# 12vTo5vPowerSupplyBoard.net
KiCad netlist of a schematic drawn in EAGLE
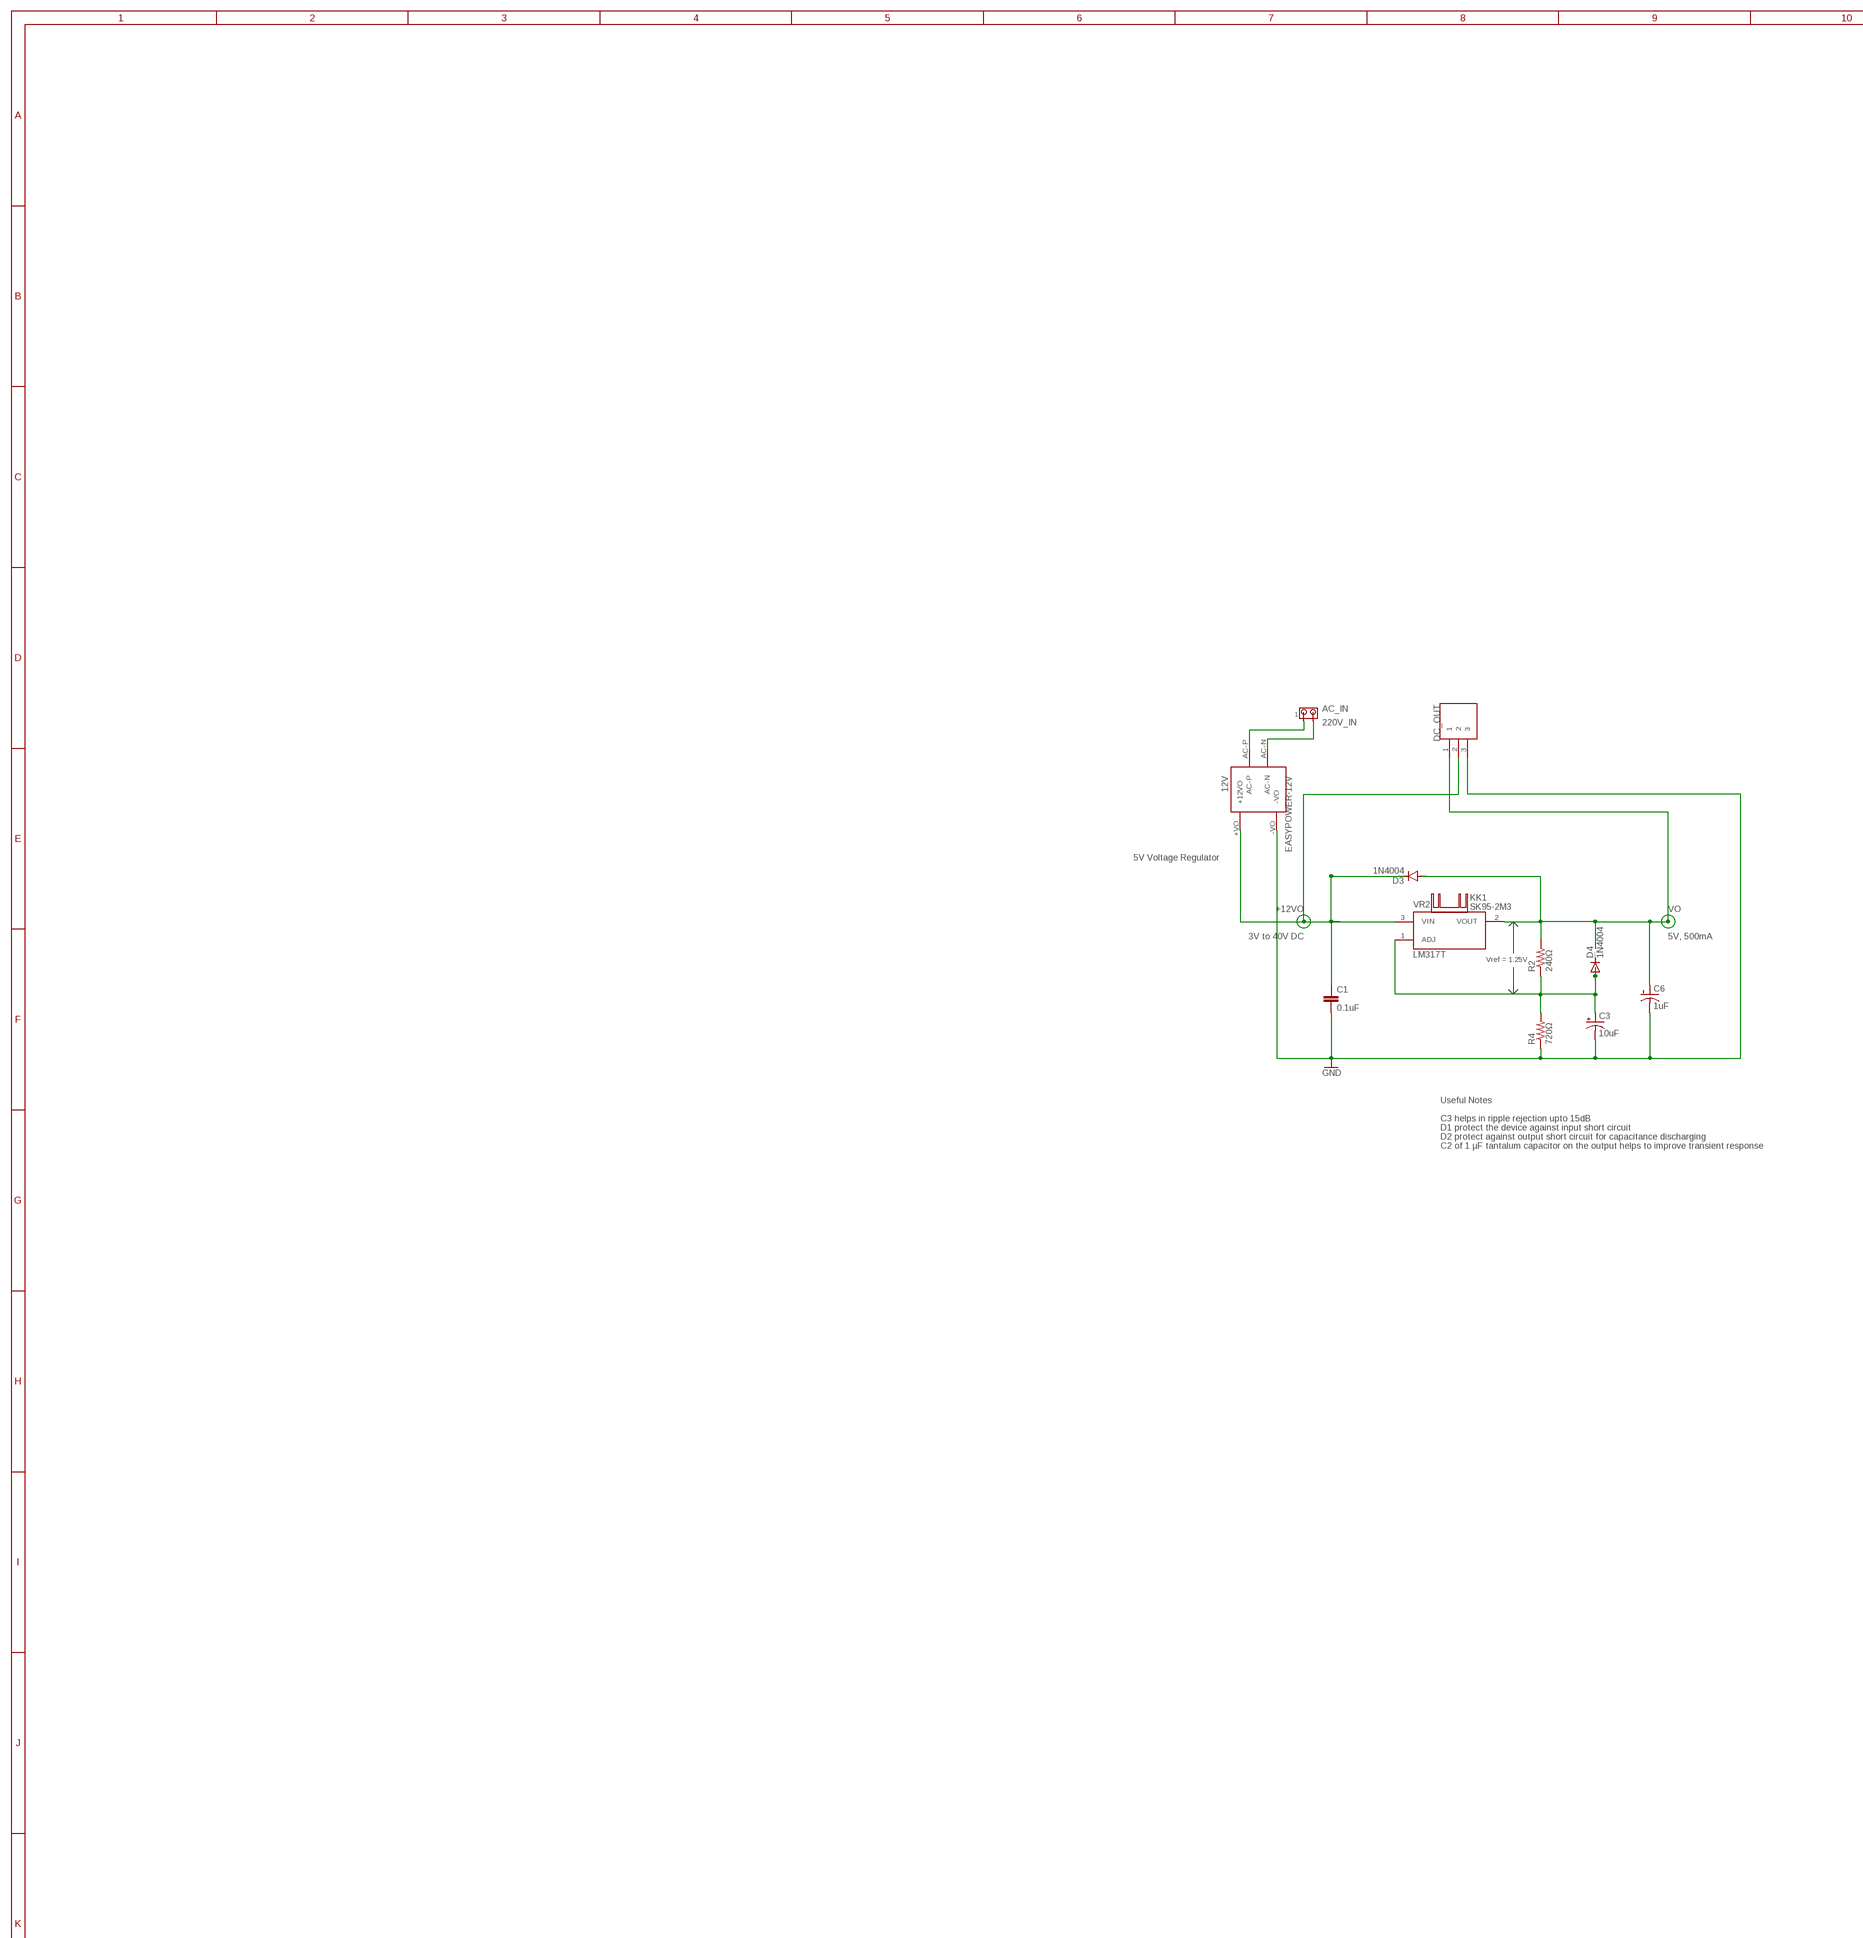
[diagram p0: schematic, sheet 1, part 1 of 3]
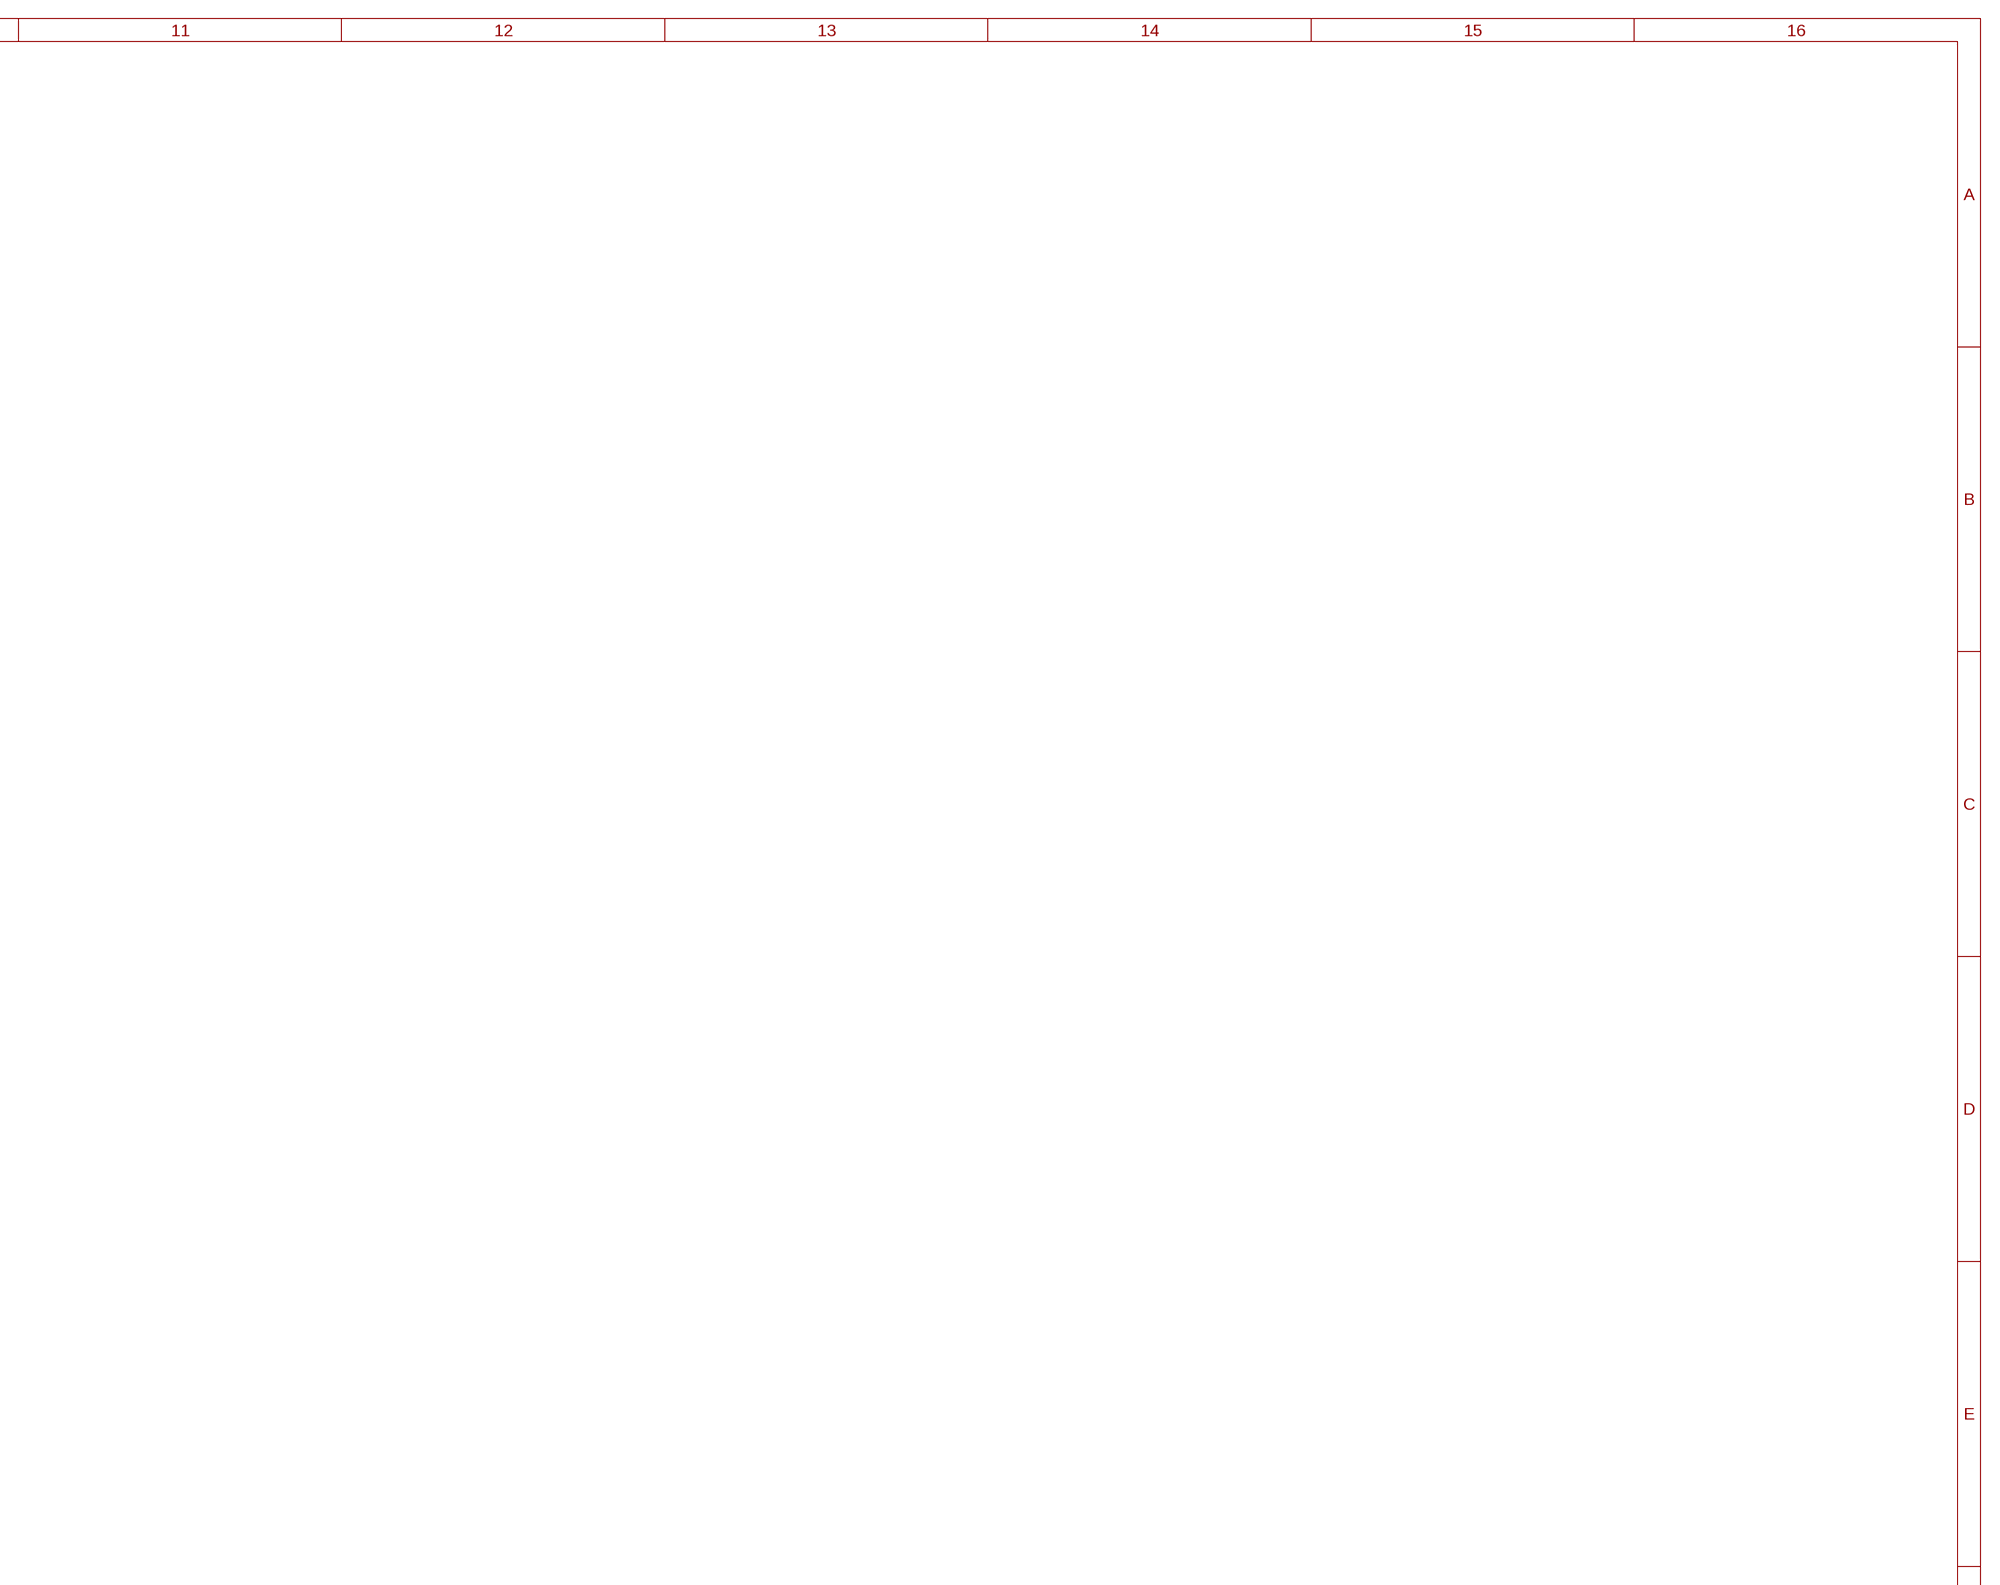
[diagram p1: schematic, sheet 1, part 2 of 3]
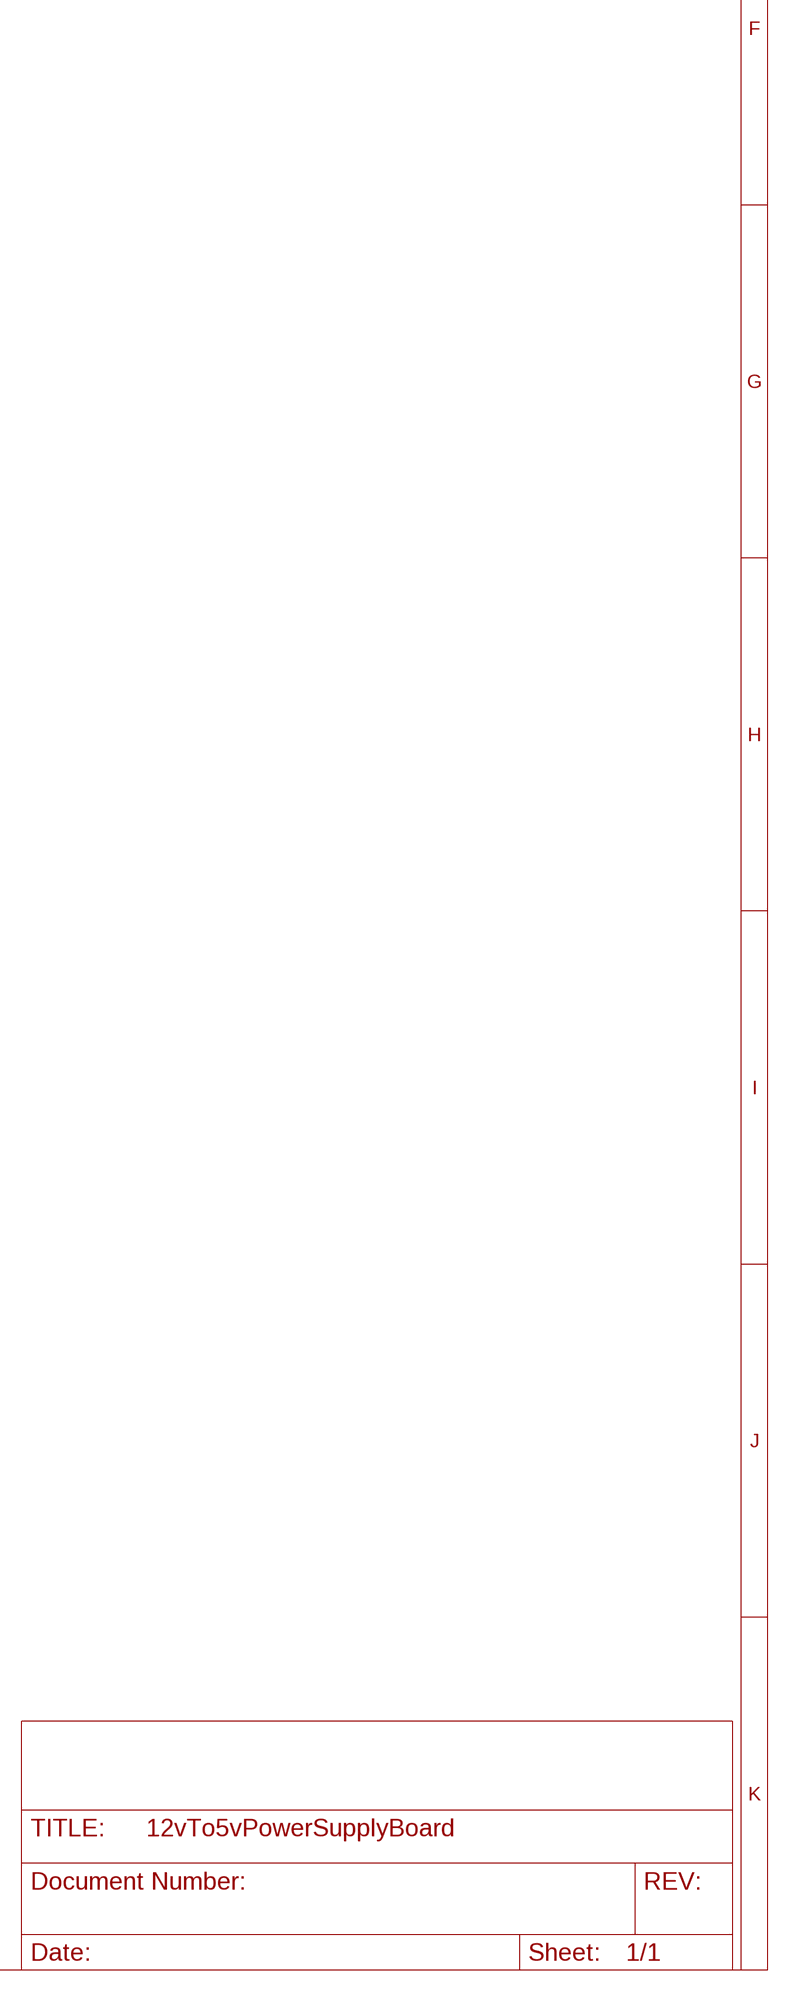
[diagram p2: schematic, sheet 1, part 3 of 3]

(export (version "E")
  (design (tool "Eeschema 10.0.6"))
  (components
    (comp (ref "AC_IN")
      (value "220V_IN")
      (footprint "eagle-import:1X2MTA")
      (libsource (lib "eagle-import") (part "MTA02-156"))
    )
    (comp (ref "C1")
      (value "0.1uF")
      (footprint "eagle-import:C2.5-2")
      (libsource (lib "eagle-import") (part "C2.5/2"))
    )
    (comp (ref "C3")
      (value "10uF")
      (footprint "eagle-import:E2,5-5")
      (libsource (lib "eagle-import") (part "CPOL-USE2.5-5"))
    )
    (comp (ref "C6")
      (value "1uF")
      (footprint "eagle-import:E2,5-5")
      (libsource (lib "eagle-import") (part "CPOL-USE2.5-5"))
    )
    (comp (ref "D3")
      (value "1N4004")
      (footprint "eagle-import:DO41-10")
      (libsource (lib "eagle-import") (part "1N4004"))
    )
    (comp (ref "D4")
      (value "1N4004")
      (footprint "eagle-import:DO41-10")
      (libsource (lib "eagle-import") (part "1N4004"))
    )
    (comp (ref "DC_OUT")
      (value "440052-3")
      (footprint "eagle-import:TE_440052-3")
      (fields (field (name "MF") "TE Connectivity"))
      (libsource (lib "eagle-import") (part "440052-3"))
    )
    (comp (ref "EASYPOWER-12V")
      (value "12V")
      (footprint "eagle-import:SO12V200")
      (libsource (lib "eagle-import") (part "SO12V200"))
    )
    (comp (ref "KK1")
      (value "SK95-2M3")
      (footprint "eagle-import:SK95-2M3")
      (libsource (lib "eagle-import") (part "SK95-2M3"))
    )
    (comp (ref "R2")
      (value "240Ω")
      (footprint "eagle-import:0204V")
      (libsource (lib "eagle-import") (part "R-US_0204/2V"))
    )
    (comp (ref "R4")
      (value "720Ω")
      (footprint "eagle-import:0204V")
      (libsource (lib "eagle-import") (part "R-US_0204/2V"))
    )
    (comp (ref "VR2")
      (value "LM317T")
      (footprint "eagle-import:TO254P1054X470X1955-3")
      (fields (field (name "MF") "Texas Instruments"))
      (libsource (lib "eagle-import") (part "LM317T"))
    )
  )
  (nets
    (net (code "1") (name "/+12VO") (class "Default")
      (node (ref "C1") (pin "1") (pinfunction "1_1") (pintype "passive"))
      (node (ref "D3") (pin "C") (pinfunction "C_C") (pintype "passive"))
      (node (ref "DC_OUT") (pin "2") (pinfunction "2_2") (pintype "passive"))
      (node (ref "EASYPOWER-12V") (pin "+VO") (pinfunction "+12VO_+VO") (pintype "power_in"))
      (node (ref "VR2") (pin "3") (pinfunction "VIN_3") (pintype "input"))
    )
    (net (code "2") (name "/VO") (class "Default")
      (node (ref "C6") (pin "+") (pinfunction "+_+") (pintype "passive"))
      (node (ref "D3") (pin "A") (pinfunction "A_A") (pintype "passive"))
      (node (ref "DC_OUT") (pin "1") (pinfunction "1_1") (pintype "passive"))
      (node (ref "R2") (pin "2") (pinfunction "2_2") (pintype "passive"))
      (node (ref "VR2") (pin "2") (pinfunction "VOUT_2") (pintype "output"))
    )
    (net (code "3") (name "GND") (class "Default")
      (node (ref "C1") (pin "2") (pinfunction "2_2") (pintype "passive"))
      (node (ref "C3") (pin "-") (pinfunction "-_-") (pintype "passive"))
      (node (ref "C6") (pin "-") (pinfunction "-_-") (pintype "passive"))
      (node (ref "DC_OUT") (pin "3") (pinfunction "3_3") (pintype "passive"))
      (node (ref "EASYPOWER-12V") (pin "-VO") (pinfunction "-VO_-VO") (pintype "power_in"))
      (node (ref "R4") (pin "1") (pinfunction "1_1") (pintype "passive"))
    )
    (net (code "4") (name "Net-(AC_IN-Pad1)") (class "Default")
      (node (ref "AC_IN") (pin "1") (pinfunction "1_1") (pintype "passive"))
      (node (ref "EASYPOWER-12V") (pin "AC-P") (pinfunction "AC-P_AC-P") (pintype "input"))
    )
    (net (code "5") (name "Net-(AC_IN-Pad2)") (class "Default")
      (node (ref "AC_IN") (pin "2") (pinfunction "2_2") (pintype "passive"))
      (node (ref "EASYPOWER-12V") (pin "AC-N") (pinfunction "AC-N_AC-N") (pintype "input"))
    )
    (net (code "6") (name "Net-(VR2-ADJ)") (class "Default")
      (node (ref "C3") (pin "+") (pinfunction "+_+") (pintype "passive"))
      (node (ref "D4") (pin "A") (pinfunction "A_A") (pintype "passive"))
      (node (ref "R2") (pin "1") (pinfunction "1_1") (pintype "passive"))
      (node (ref "R4") (pin "2") (pinfunction "2_2") (pintype "passive"))
      (node (ref "VR2") (pin "1") (pinfunction "ADJ_1") (pintype "input"))
    )
    (net (code "7") (name "unconnected-(D4-PadC)") (class "Default")
      (node (ref "D4") (pin "C") (pinfunction "C_C") (pintype "passive"))
    )
  )
)
